# Smart_Driver_Adapter_Caps.net
KiCad netlist of a schematic drawn in EAGLE
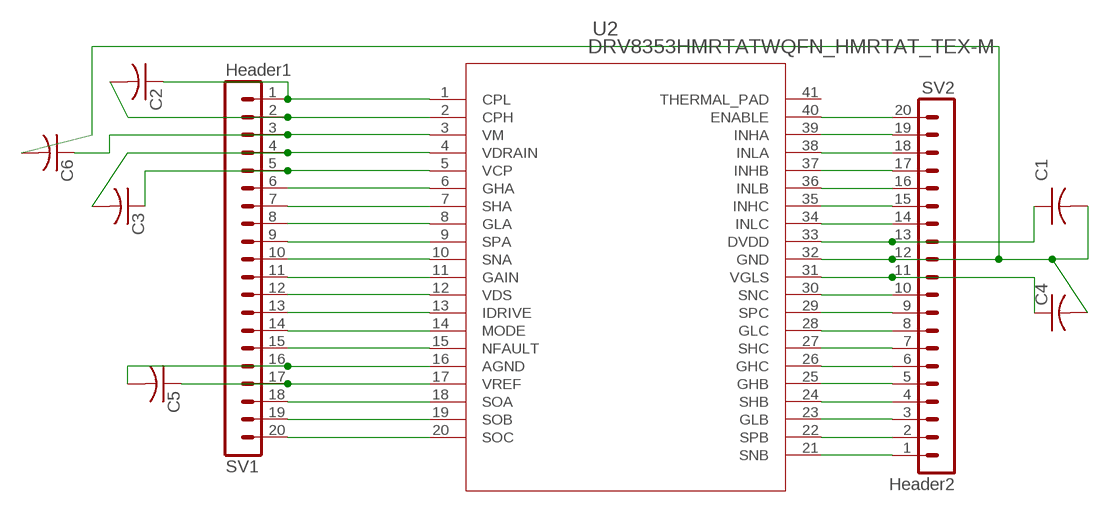
[diagram p0: schematic, sheet 1]

(export (version "E")
  (design (tool "Eeschema 10.0.6"))
  (components
    (comp (ref "C1")
      (value "C-USC0603K")
      (footprint "eagle-import:C0603K")
      (libsource (lib "eagle-import") (part "C-USC0603K"))
    )
    (comp (ref "C2")
      (value "C-USC1206K")
      (footprint "eagle-import:C1206K")
      (libsource (lib "eagle-import") (part "C-USC1206K"))
    )
    (comp (ref "C3")
      (value "C-USC0805K")
      (footprint "eagle-import:C0805K")
      (libsource (lib "eagle-import") (part "C-USC0805K"))
    )
    (comp (ref "C4")
      (value "C-USC0805K")
      (footprint "eagle-import:C0805K")
      (libsource (lib "eagle-import") (part "C-USC0805K"))
    )
    (comp (ref "C5")
      (value "C-USC0201")
      (footprint "eagle-import:C0201")
      (libsource (lib "eagle-import") (part "C-USC0201"))
    )
    (comp (ref "C6")
      (value "C-USC1206K")
      (footprint "eagle-import:C1206K")
      (libsource (lib "eagle-import") (part "C-USC1206K"))
    )
    (comp (ref "SV1")
      (value "Header1")
      (footprint "eagle-import:MA20-1")
      (libsource (lib "eagle-import") (part "MA20-1"))
    )
    (comp (ref "SV2")
      (value "Header2")
      (footprint "eagle-import:MA20-1")
      (libsource (lib "eagle-import") (part "MA20-1"))
    )
    (comp (ref "U2")
      (value "DRV8353HMRTATWQFN_HMRTAT_TEX-M")
      (footprint "eagle-import:WQFN_HMRTAT_TEX-M")
      (fields
        (field (name "MANUFACTURER_PART_NUMBER") "DRV8353HMRTAT")
        (field (name "COPYRIGHT") "Copyright (C) 2021 Ultra Librarian. All rights reserved.")
      )
      (libsource (lib "eagle-import") (part "DRV8353HMRTATWQFN_HMRTAT_TEX-M"))
    )
  )
  (nets
    (net (code "1") (name "Net-(U2-AGND)") (class "Default")
      (node (ref "C5") (pin "2") (pinfunction "2_2") (pintype "passive"))
      (node (ref "SV1") (pin "16") (pinfunction "16_16") (pintype "passive"))
      (node (ref "U2") (pin "16") (pinfunction "AGND_16") (pintype "passive"))
    )
    (net (code "2") (name "Net-(U2-CPH)") (class "Default")
      (node (ref "C2") (pin "2") (pinfunction "2_2") (pintype "passive"))
      (node (ref "SV1") (pin "2") (pinfunction "2_2") (pintype "passive"))
      (node (ref "U2") (pin "2") (pinfunction "CPH_2") (pintype "passive"))
    )
    (net (code "3") (name "Net-(U2-CPL)") (class "Default")
      (node (ref "C2") (pin "1") (pinfunction "1_1") (pintype "passive"))
      (node (ref "SV1") (pin "1") (pinfunction "1_1") (pintype "passive"))
      (node (ref "U2") (pin "1") (pinfunction "CPL_1") (pintype "passive"))
    )
    (net (code "4") (name "Net-(U2-DVDD)") (class "Default")
      (node (ref "C1") (pin "1") (pinfunction "1_1") (pintype "passive"))
      (node (ref "SV2") (pin "13") (pinfunction "13_13") (pintype "passive"))
      (node (ref "U2") (pin "33") (pinfunction "DVDD_33") (pintype "power_in"))
    )
    (net (code "5") (name "Net-(U2-ENABLE)") (class "Default")
      (node (ref "SV2") (pin "20") (pinfunction "20_20") (pintype "passive"))
      (node (ref "U2") (pin "40") (pinfunction "ENABLE_40") (pintype "passive"))
    )
    (net (code "6") (name "Net-(U2-GAIN)") (class "Default")
      (node (ref "SV1") (pin "11") (pinfunction "11_11") (pintype "passive"))
      (node (ref "U2") (pin "11") (pinfunction "GAIN_11") (pintype "passive"))
    )
    (net (code "7") (name "Net-(U2-GHA)") (class "Default")
      (node (ref "SV1") (pin "6") (pinfunction "6_6") (pintype "passive"))
      (node (ref "U2") (pin "6") (pinfunction "GHA_6") (pintype "passive"))
    )
    (net (code "8") (name "Net-(U2-GHB)") (class "Default")
      (node (ref "SV2") (pin "5") (pinfunction "5_5") (pintype "passive"))
      (node (ref "U2") (pin "25") (pinfunction "GHB_25") (pintype "passive"))
    )
    (net (code "9") (name "Net-(U2-GHC)") (class "Default")
      (node (ref "SV2") (pin "6") (pinfunction "6_6") (pintype "passive"))
      (node (ref "U2") (pin "26") (pinfunction "GHC_26") (pintype "passive"))
    )
    (net (code "10") (name "Net-(U2-GLA)") (class "Default")
      (node (ref "SV1") (pin "8") (pinfunction "8_8") (pintype "passive"))
      (node (ref "U2") (pin "8") (pinfunction "GLA_8") (pintype "passive"))
    )
    (net (code "11") (name "Net-(U2-GLB)") (class "Default")
      (node (ref "SV2") (pin "3") (pinfunction "3_3") (pintype "passive"))
      (node (ref "U2") (pin "23") (pinfunction "GLB_23") (pintype "passive"))
    )
    (net (code "12") (name "Net-(U2-GLC)") (class "Default")
      (node (ref "SV2") (pin "8") (pinfunction "8_8") (pintype "passive"))
      (node (ref "U2") (pin "28") (pinfunction "GLC_28") (pintype "passive"))
    )
    (net (code "13") (name "Net-(U2-GND)") (class "Default")
      (node (ref "C1") (pin "2") (pinfunction "2_2") (pintype "passive"))
      (node (ref "C4") (pin "2") (pinfunction "2_2") (pintype "passive"))
      (node (ref "C6") (pin "2") (pinfunction "2_2") (pintype "passive"))
      (node (ref "SV2") (pin "12") (pinfunction "12_12") (pintype "passive"))
      (node (ref "U2") (pin "32") (pinfunction "GND_32") (pintype "passive"))
    )
    (net (code "14") (name "Net-(U2-IDRIVE)") (class "Default")
      (node (ref "SV1") (pin "13") (pinfunction "13_13") (pintype "passive"))
      (node (ref "U2") (pin "13") (pinfunction "IDRIVE_13") (pintype "passive"))
    )
    (net (code "15") (name "Net-(U2-INHA)") (class "Default")
      (node (ref "SV2") (pin "19") (pinfunction "19_19") (pintype "passive"))
      (node (ref "U2") (pin "39") (pinfunction "INHA_39") (pintype "input"))
    )
    (net (code "16") (name "Net-(U2-INHB)") (class "Default")
      (node (ref "SV2") (pin "17") (pinfunction "17_17") (pintype "passive"))
      (node (ref "U2") (pin "37") (pinfunction "INHB_37") (pintype "input"))
    )
    (net (code "17") (name "Net-(U2-INHC)") (class "Default")
      (node (ref "SV2") (pin "15") (pinfunction "15_15") (pintype "passive"))
      (node (ref "U2") (pin "35") (pinfunction "INHC_35") (pintype "input"))
    )
    (net (code "18") (name "Net-(U2-INLA)") (class "Default")
      (node (ref "SV2") (pin "18") (pinfunction "18_18") (pintype "passive"))
      (node (ref "U2") (pin "38") (pinfunction "INLA_38") (pintype "input"))
    )
    (net (code "19") (name "Net-(U2-INLB)") (class "Default")
      (node (ref "SV2") (pin "16") (pinfunction "16_16") (pintype "passive"))
      (node (ref "U2") (pin "36") (pinfunction "INLB_36") (pintype "input"))
    )
    (net (code "20") (name "Net-(U2-INLC)") (class "Default")
      (node (ref "SV2") (pin "14") (pinfunction "14_14") (pintype "passive"))
      (node (ref "U2") (pin "34") (pinfunction "INLC_34") (pintype "input"))
    )
    (net (code "21") (name "Net-(U2-MODE)") (class "Default")
      (node (ref "SV1") (pin "14") (pinfunction "14_14") (pintype "passive"))
      (node (ref "U2") (pin "14") (pinfunction "MODE_14") (pintype "passive"))
    )
    (net (code "22") (name "Net-(U2-NFAULT)") (class "Default")
      (node (ref "SV1") (pin "15") (pinfunction "15_15") (pintype "passive"))
      (node (ref "U2") (pin "15") (pinfunction "NFAULT_15") (pintype "passive"))
    )
    (net (code "23") (name "Net-(U2-SHA)") (class "Default")
      (node (ref "SV1") (pin "7") (pinfunction "7_7") (pintype "passive"))
      (node (ref "U2") (pin "7") (pinfunction "SHA_7") (pintype "passive"))
    )
    (net (code "24") (name "Net-(U2-SHB)") (class "Default")
      (node (ref "SV2") (pin "4") (pinfunction "4_4") (pintype "passive"))
      (node (ref "U2") (pin "24") (pinfunction "SHB_24") (pintype "passive"))
    )
    (net (code "25") (name "Net-(U2-SHC)") (class "Default")
      (node (ref "SV2") (pin "7") (pinfunction "7_7") (pintype "passive"))
      (node (ref "U2") (pin "27") (pinfunction "SHC_27") (pintype "passive"))
    )
    (net (code "26") (name "Net-(U2-SNA)") (class "Default")
      (node (ref "SV1") (pin "10") (pinfunction "10_10") (pintype "passive"))
      (node (ref "U2") (pin "10") (pinfunction "SNA_10") (pintype "passive"))
    )
    (net (code "27") (name "Net-(U2-SNB)") (class "Default")
      (node (ref "SV2") (pin "1") (pinfunction "1_1") (pintype "passive"))
      (node (ref "U2") (pin "21") (pinfunction "SNB_21") (pintype "passive"))
    )
    (net (code "28") (name "Net-(U2-SNC)") (class "Default")
      (node (ref "SV2") (pin "10") (pinfunction "10_10") (pintype "passive"))
      (node (ref "U2") (pin "30") (pinfunction "SNC_30") (pintype "passive"))
    )
    (net (code "29") (name "Net-(U2-SOA)") (class "Default")
      (node (ref "SV1") (pin "18") (pinfunction "18_18") (pintype "passive"))
      (node (ref "U2") (pin "18") (pinfunction "SOA_18") (pintype "passive"))
    )
    (net (code "30") (name "Net-(U2-SOB)") (class "Default")
      (node (ref "SV1") (pin "19") (pinfunction "19_19") (pintype "passive"))
      (node (ref "U2") (pin "19") (pinfunction "SOB_19") (pintype "passive"))
    )
    (net (code "31") (name "Net-(U2-SOC)") (class "Default")
      (node (ref "SV1") (pin "20") (pinfunction "20_20") (pintype "passive"))
      (node (ref "U2") (pin "20") (pinfunction "SOC_20") (pintype "passive"))
    )
    (net (code "32") (name "Net-(U2-SPA)") (class "Default")
      (node (ref "SV1") (pin "9") (pinfunction "9_9") (pintype "passive"))
      (node (ref "U2") (pin "9") (pinfunction "SPA_9") (pintype "passive"))
    )
    (net (code "33") (name "Net-(U2-SPB)") (class "Default")
      (node (ref "SV2") (pin "2") (pinfunction "2_2") (pintype "passive"))
      (node (ref "U2") (pin "22") (pinfunction "SPB_22") (pintype "passive"))
    )
    (net (code "34") (name "Net-(U2-SPC)") (class "Default")
      (node (ref "SV2") (pin "9") (pinfunction "9_9") (pintype "passive"))
      (node (ref "U2") (pin "29") (pinfunction "SPC_29") (pintype "passive"))
    )
    (net (code "35") (name "Net-(U2-VCP)") (class "Default")
      (node (ref "C3") (pin "1") (pinfunction "1_1") (pintype "passive"))
      (node (ref "SV1") (pin "5") (pinfunction "5_5") (pintype "passive"))
      (node (ref "U2") (pin "5") (pinfunction "VCP_5") (pintype "passive"))
    )
    (net (code "36") (name "Net-(U2-VDRAIN)") (class "Default")
      (node (ref "C3") (pin "2") (pinfunction "2_2") (pintype "passive"))
      (node (ref "SV1") (pin "4") (pinfunction "4_4") (pintype "passive"))
      (node (ref "U2") (pin "4") (pinfunction "VDRAIN_4") (pintype "passive"))
    )
    (net (code "37") (name "Net-(U2-VDS)") (class "Default")
      (node (ref "SV1") (pin "12") (pinfunction "12_12") (pintype "passive"))
      (node (ref "U2") (pin "12") (pinfunction "VDS_12") (pintype "passive"))
    )
    (net (code "38") (name "Net-(U2-VGLS)") (class "Default")
      (node (ref "C4") (pin "1") (pinfunction "1_1") (pintype "passive"))
      (node (ref "SV2") (pin "11") (pinfunction "11_11") (pintype "passive"))
      (node (ref "U2") (pin "31") (pinfunction "VGLS_31") (pintype "passive"))
    )
    (net (code "39") (name "Net-(U2-VM)") (class "Default")
      (node (ref "C6") (pin "1") (pinfunction "1_1") (pintype "passive"))
      (node (ref "SV1") (pin "3") (pinfunction "3_3") (pintype "passive"))
      (node (ref "U2") (pin "3") (pinfunction "VM_3") (pintype "passive"))
    )
    (net (code "40") (name "Net-(U2-VREF)") (class "Default")
      (node (ref "C5") (pin "1") (pinfunction "1_1") (pintype "passive"))
      (node (ref "SV1") (pin "17") (pinfunction "17_17") (pintype "passive"))
      (node (ref "U2") (pin "17") (pinfunction "VREF_17") (pintype "power_in"))
    )
    (net (code "41") (name "unconnected-(U2-THERMAL_PAD-Pad41)") (class "Default")
      (node (ref "U2") (pin "41") (pinfunction "THERMAL_PAD_41") (pintype "passive"))
    )
  )
)
